# Sheet9.net
KiCad netlist of a schematic drawn in Altium Designer
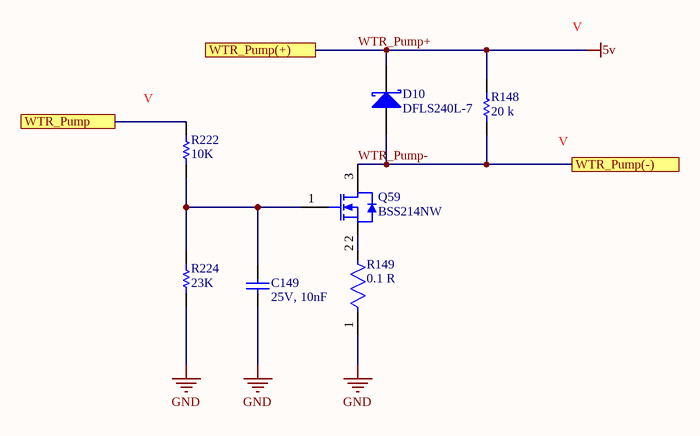
[diagram p0: Sheet9.SchDoc]

(export (version "E")
  (design (tool "Eeschema 10.0.6"))
  (components
    (comp (ref "C149")
      (value "25V, 10nF")
      (footprint "CAPC2013X94X50LL20T25")
      (fields
        (field (name "MANUFACTURER") "AVX Interconnect / Elco")
        (field (name "PART NUMBER") "08053C103JAT2A")
      )
      (libsource (lib "Altium Content Vault") (part "CAP"))
    )
    (comp (ref "D10")
      (value "DFLS240L-7")
      (footprint "DIOD-POWERDI123-2_A_V")
      (description "Low VF Schottky Barrier Rectifier, 2 A, 40 V, -55 to 125 degC, 2-Pin SMD, RoHS, Tape and Reel")
      (fields (field (name "MANUFACTURER") "Diodes Inc"))
      (libsource (lib "Altium Content Vault") (part "DSKY-AK-2"))
    )
    (comp (ref "Q59")
      (value "BSS214NW")
      (footprint "INF-PG-SOT-323_N")
      (fields (field (name "MANUFACTURER") "Infineon"))
      (libsource (lib "Altium Content Vault") (part "INF-NEMOS-GSD-3"))
    )
    (comp (ref "R148")
      (value "20 k")
      (description "Resistor")
      (libsource (lib "Simulation Generic Components") (part "Resistor"))
    )
    (comp (ref "R149")
      (value "0.1 R")
      (footprint "FP-RL0603-0_55-MFG")
      (description "RES 0.1 OHM 1% 1/10W 0603")
      (fields (field (name "TOLERANCE") "1%"))
      (libsource (lib "Altium Content Vault") (part "1029c3af85768c4190bb7ad29bc67b5"))
    )
    (comp (ref "R222")
      (value "10K")
      (description "Resistor")
      (libsource (lib "Simulation Generic Components") (part "Resistor"))
    )
    (comp (ref "R224")
      (value "23K")
      (description "Resistor")
      (libsource (lib "Simulation Generic Components") (part "Resistor"))
    )
  )
  (nets
    (net (code "1") (name "/WTR_Pump") (class "Default")
      (node (ref "R222") (pin "2") (pinfunction "2_2") (pintype "passive"))
    )
    (net (code "2") (name "/WTR_Pump-") (class "Default")
      (node (ref "D10") (pin "1") (pinfunction "A_1") (pintype "passive"))
      (node (ref "Q59") (pin "3") (pinfunction "DRAIN_3") (pintype "passive"))
      (node (ref "R148") (pin "1") (pinfunction "1_1") (pintype "passive"))
    )
    (net (code "3") (name "5v") (class "Default")
      (node (ref "D10") (pin "2") (pinfunction "K_2") (pintype "passive"))
      (node (ref "R148") (pin "2") (pinfunction "2_2") (pintype "passive"))
    )
    (net (code "4") (name "GND") (class "Default")
      (node (ref "C149") (pin "1") (pinfunction "1_1") (pintype "passive"))
      (node (ref "R149") (pin "1") (pinfunction "1_1") (pintype "passive"))
      (node (ref "R224") (pin "1") (pinfunction "1_1") (pintype "passive"))
    )
    (net (code "5") (name "Net-(Q59-GATE)") (class "Default")
      (node (ref "C149") (pin "2") (pinfunction "2_2") (pintype "passive"))
      (node (ref "Q59") (pin "1") (pinfunction "GATE_1") (pintype "passive"))
      (node (ref "R222") (pin "1") (pinfunction "1_1") (pintype "passive"))
      (node (ref "R224") (pin "2") (pinfunction "2_2") (pintype "passive"))
    )
    (net (code "6") (name "Net-(Q59-SOURCE)") (class "Default")
      (node (ref "Q59") (pin "2") (pinfunction "SOURCE_2") (pintype "passive"))
      (node (ref "R149") (pin "2") (pinfunction "2_2") (pintype "passive"))
    )
  )
)
